# Zio_Qwiic_Light_Sensor_TSL2561.net
KiCad netlist of a schematic drawn in EAGLE
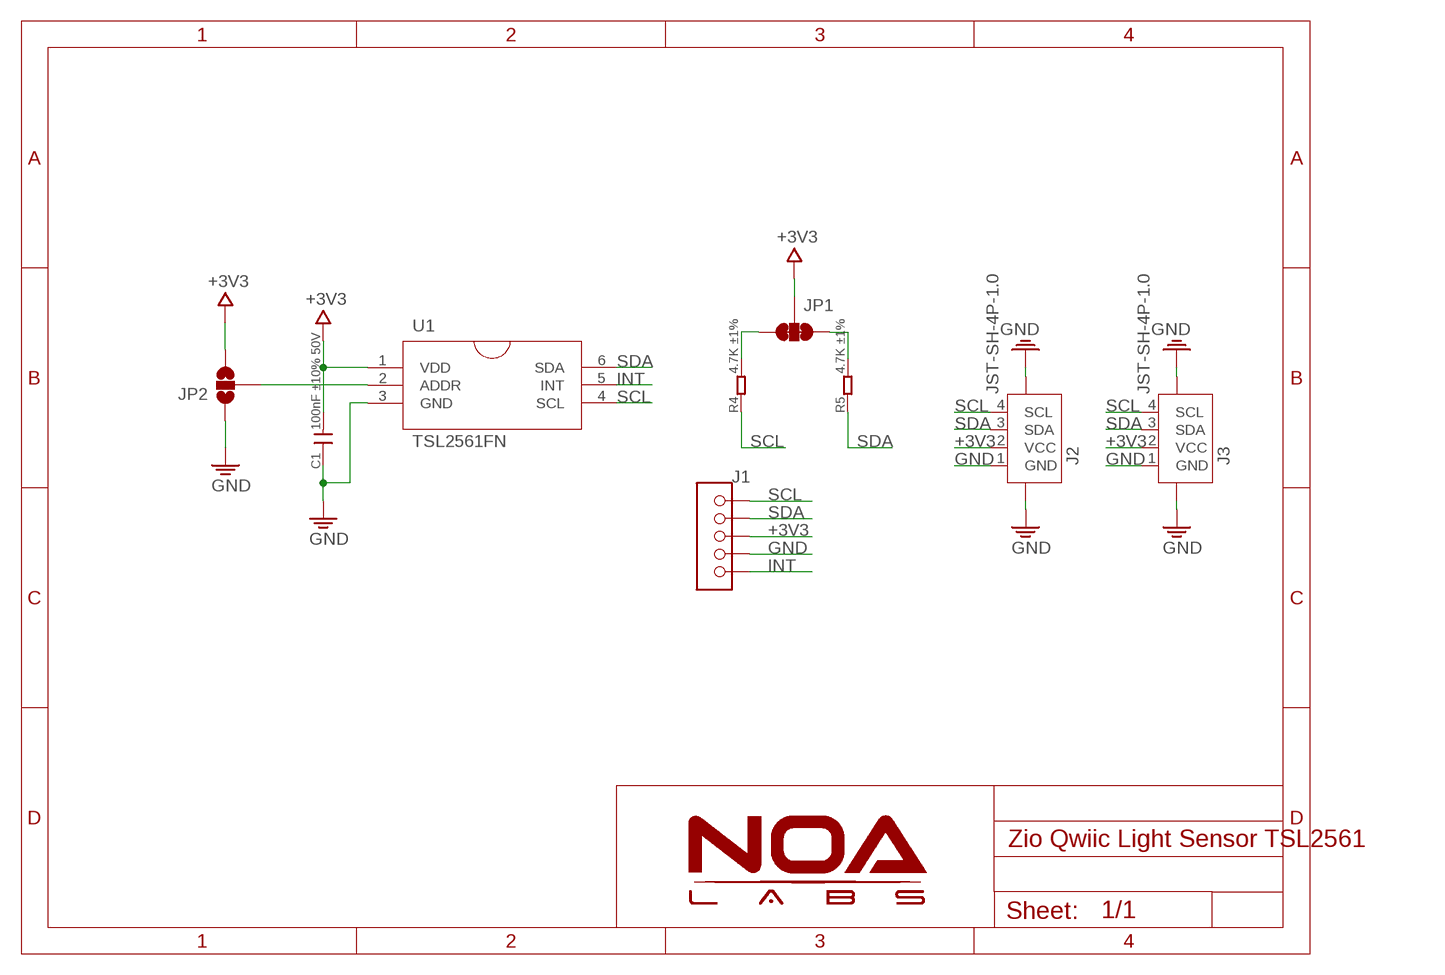
[diagram p0: schematic, sheet 1]

(export (version "E")
  (design (tool "Eeschema 10.0.6"))
  (components
    (comp (ref "C1")
      (value "100nF ±10% 50V")
      (footprint "eagle-import:C0603")
      (libsource (lib "eagle-import") (part "C-0603"))
    )
    (comp (ref "J1")
      (value "HEADER-5P-2.54")
      (footprint "eagle-import:5P-2.54")
      (libsource (lib "eagle-import") (part "HEADER-5P-2.54"))
    )
    (comp (ref "J2")
      (value "JST-SH-4P-1.0")
      (footprint "eagle-import:JST-SH-4P")
      (libsource (lib "eagle-import") (part "JST-SH-4P-1.0"))
    )
    (comp (ref "J3")
      (value "JST-SH-4P-1.0")
      (footprint "eagle-import:JST-SH-4P")
      (libsource (lib "eagle-import") (part "JST-SH-4P-1.0"))
    )
    (comp (ref "JP1")
      (value "SMT-JUMPER_3_2-NC_TRACE")
      (footprint "eagle-import:SMT-JUMPER_3_2-NC_TRACE")
      (libsource (lib "eagle-import") (part "SMT-JUMPER_3_2-NC_TRACE"))
    )
    (comp (ref "JP2")
      (value "JUMPER-SMT_3_2-NC_PASTE_NOCREM")
      (footprint "eagle-import:SMT-JUMPER_3_2-NC_PASTE_SILK_NOCREM")
      (libsource (lib "eagle-import") (part "JUMPER-SMT_3_2-NC_PASTE_NOCREM"))
    )
    (comp (ref "R4")
      (value "4.7K ±1%")
      (footprint "eagle-import:R0603")
      (libsource (lib "eagle-import") (part "R-0603"))
    )
    (comp (ref "R5")
      (value "4.7K ±1%")
      (footprint "eagle-import:R0603")
      (libsource (lib "eagle-import") (part "R-0603"))
    )
    (comp (ref "U1")
      (value "TSL2561FN")
      (footprint "eagle-import:FN6")
      (libsource (lib "eagle-import") (part "TSL2561FN"))
    )
  )
  (nets
    (net (code "1") (name "+3V3") (class "Default")
      (node (ref "C1") (pin "2") (pinfunction "2_2") (pintype "passive"))
      (node (ref "J1") (pin "3") (pinfunction "3_3") (pintype "bidirectional"))
      (node (ref "J2") (pin "2") (pinfunction "VCC_2") (pintype "bidirectional"))
      (node (ref "J3") (pin "2") (pinfunction "VCC_2") (pintype "bidirectional"))
      (node (ref "JP1") (pin "2") (pinfunction "2_2") (pintype "passive"))
      (node (ref "JP2") (pin "3") (pinfunction "3_3") (pintype "passive"))
      (node (ref "U1") (pin "1") (pinfunction "VDD_1") (pintype "bidirectional"))
    )
    (net (code "2") (name "/INT") (class "Default")
      (node (ref "J1") (pin "5") (pinfunction "5_5") (pintype "bidirectional"))
      (node (ref "U1") (pin "5") (pinfunction "INT_5") (pintype "bidirectional"))
    )
    (net (code "3") (name "/SCL") (class "Default")
      (node (ref "J1") (pin "1") (pinfunction "1_1") (pintype "bidirectional"))
      (node (ref "J2") (pin "4") (pinfunction "SCL_4") (pintype "bidirectional"))
      (node (ref "J3") (pin "4") (pinfunction "SCL_4") (pintype "bidirectional"))
      (node (ref "R4") (pin "1") (pinfunction "1_1") (pintype "passive"))
      (node (ref "U1") (pin "4") (pinfunction "SCL_4") (pintype "bidirectional"))
    )
    (net (code "4") (name "/SDA") (class "Default")
      (node (ref "J1") (pin "2") (pinfunction "2_2") (pintype "bidirectional"))
      (node (ref "J2") (pin "3") (pinfunction "SDA_3") (pintype "bidirectional"))
      (node (ref "J3") (pin "3") (pinfunction "SDA_3") (pintype "bidirectional"))
      (node (ref "R5") (pin "1") (pinfunction "1_1") (pintype "passive"))
      (node (ref "U1") (pin "6") (pinfunction "SDA_6") (pintype "bidirectional"))
    )
    (net (code "5") (name "GND") (class "Default")
      (node (ref "C1") (pin "1") (pinfunction "1_1") (pintype "passive"))
      (node (ref "J1") (pin "4") (pinfunction "4_4") (pintype "bidirectional"))
      (node (ref "J2") (pin "1") (pinfunction "GND_1") (pintype "bidirectional"))
      (node (ref "J2") (pin "NC1") (pinfunction "5_NC1") (pintype "bidirectional"))
      (node (ref "J2") (pin "NC2") (pinfunction "6_NC2") (pintype "bidirectional"))
      (node (ref "J3") (pin "1") (pinfunction "GND_1") (pintype "bidirectional"))
      (node (ref "J3") (pin "NC1") (pinfunction "5_NC1") (pintype "bidirectional"))
      (node (ref "J3") (pin "NC2") (pinfunction "6_NC2") (pintype "bidirectional"))
      (node (ref "JP2") (pin "1") (pinfunction "1_1") (pintype "passive"))
      (node (ref "U1") (pin "3") (pinfunction "GND_3") (pintype "bidirectional"))
    )
    (net (code "6") (name "Net-(JP1-Pad1)") (class "Default")
      (node (ref "JP1") (pin "1") (pinfunction "1_1") (pintype "passive"))
      (node (ref "R5") (pin "2") (pinfunction "2_2") (pintype "passive"))
    )
    (net (code "7") (name "Net-(JP1-Pad3)") (class "Default")
      (node (ref "JP1") (pin "3") (pinfunction "3_3") (pintype "passive"))
      (node (ref "R4") (pin "2") (pinfunction "2_2") (pintype "passive"))
    )
    (net (code "8") (name "Net-(U1-ADDR)") (class "Default")
      (node (ref "JP2") (pin "2") (pinfunction "2_2") (pintype "passive"))
      (node (ref "U1") (pin "2") (pinfunction "ADDR_2") (pintype "bidirectional"))
    )
  )
)
